# 3_buck.net
KiCad netlist of a schematic drawn in Altium Designer
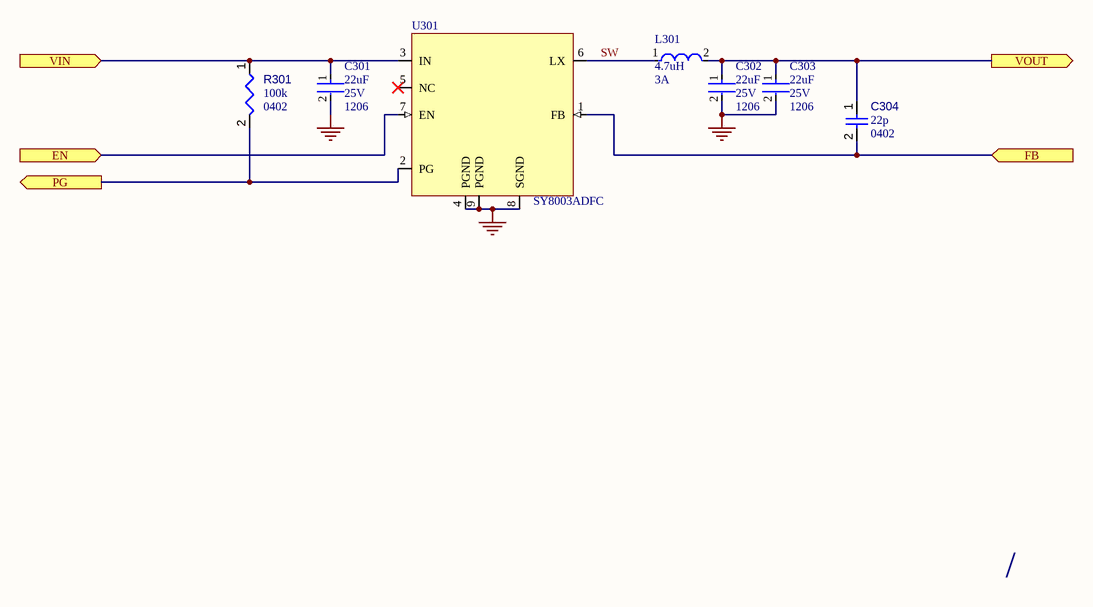
[diagram p0: 3 buck.SchDoc]

(export (version "E")
  (design (tool "Eeschema 10.0.6"))
  (components
    (comp (ref "C301")
      (value "TMK316BBJ226ML-T")
      (footprint "FP-1206-L_3_2_0_3-W_1_6_0-MFG")
      (description "None")
      (fields
        (field (name "CAPACITANCE") "22uF")
        (field (name "VOLTAGE RATING (DC)") "25V")
        (field (name "CASE CODE (IMPERIAL)") "1206")
        (field (name "TOLERANCE") "20%")
      )
      (libsource (lib "Altium Content Vault") (part "11868f565c42a9108669ba33697ecf6"))
    )
    (comp (ref "C302")
      (value "TMK316BBJ226ML-T")
      (footprint "FP-1206-L_3_2_0_3-W_1_6_0-MFG")
      (description "None")
      (fields
        (field (name "CAPACITANCE") "22uF")
        (field (name "VOLTAGE RATING (DC)") "25V")
        (field (name "CASE CODE (IMPERIAL)") "1206")
        (field (name "TOLERANCE") "20%")
      )
      (libsource (lib "Altium Content Vault") (part "11868f565c42a9108669ba33697ecf6"))
    )
    (comp (ref "C303")
      (value "TMK316BBJ226ML-T")
      (footprint "FP-1206-L_3_2_0_3-W_1_6_0-MFG")
      (description "None")
      (fields
        (field (name "CAPACITANCE") "22uF")
        (field (name "VOLTAGE RATING (DC)") "25V")
        (field (name "CASE CODE (IMPERIAL)") "1206")
        (field (name "TOLERANCE") "20%")
      )
      (libsource (lib "Altium Content Vault") (part "11868f565c42a9108669ba33697ecf6"))
    )
    (comp (ref "C304")
      (value "22p")
      (footprint "CAPC0402(1005)60_L")
      (description "Capacitor")
      (fields (field (name "CASE/PACKAGE") "0402") (field (name "Comment") "Capacitors,0402,22p"))
      (libsource (lib "UBC Uncrewed Aircraft Systems") (part "CAP-NP-2"))
    )
    (comp (ref "L301")
      (value "IHLP2525AHER4R7M01")
      (footprint "FP-IHLP-2525AH-FP_2_413x3-MFG")
      (description "Commercial Inductors, High Saturation Series 4.7uH 3A 78mΩ 20%")
      (fields
        (field (name "INDUCTANCE") "4.7uH")
        (field (name "TOLERANCE") "20%")
        (field (name "CURRENT RATING") "3A")
      )
      (libsource (lib "Altium Content Vault") (part "725321dda6339637d4d059423bc1c3c"))
    )
    (comp (ref "R301")
      (value "100k")
      (footprint "RESC0402(1005)_L")
      (description "Resistor")
      (fields
        (field (name "CASE/PACKAGE") "0402")
        (field (name "TOLERANCE") "1%")
        (field (name "Comment") "Resistors,0402,1%,100k")
      )
      (libsource (lib "UBC Uncrewed Aircraft Systems") (part "RES-2"))
    )
    (comp (ref "U301")
      (value "SY8003ADFC")
      (footprint "DFN2x2-8")
      (description "High Efficiency 5.5V, 3A Continuous, 1MHz Synchronous Step Down Regulator")
      (fields
        (field (name "MANUFACTURER") "Silergy")
        (field (name "MANUFACTURER PART NUMBER") "High Efficiency 5.5V, 3A continuous, 1MHz")
      )
      (libsource (lib "Phils") (part "SY8003ADFC"))
    )
  )
  (nets
    (net (code "1") (name "/EN") (class "Default")
      (node (ref "U301") (pin "7") (pinfunction "EN_7") (pintype "input"))
    )
    (net (code "2") (name "/FB") (class "Default")
      (node (ref "C304") (pin "2") (pinfunction "2_2") (pintype "passive"))
      (node (ref "U301") (pin "1") (pinfunction "FB_1") (pintype "input"))
    )
    (net (code "3") (name "/PG") (class "Default")
      (node (ref "R301") (pin "2") (pinfunction "2_2") (pintype "passive"))
      (node (ref "U301") (pin "2") (pinfunction "PG_2") (pintype "open_collector"))
    )
    (net (code "4") (name "/SW") (class "Default")
      (node (ref "L301") (pin "1") (pinfunction "1_1") (pintype "passive"))
      (node (ref "U301") (pin "6") (pinfunction "LX_6") (pintype "power_in"))
    )
    (net (code "5") (name "/VIN") (class "Default")
      (node (ref "C301") (pin "1") (pinfunction "1_1") (pintype "passive"))
      (node (ref "R301") (pin "1") (pinfunction "1_1") (pintype "passive"))
      (node (ref "U301") (pin "3") (pinfunction "IN_3") (pintype "power_in"))
    )
    (net (code "6") (name "/VOUT") (class "Default")
      (node (ref "C302") (pin "1") (pinfunction "1_1") (pintype "passive"))
      (node (ref "C303") (pin "1") (pinfunction "1_1") (pintype "passive"))
      (node (ref "C304") (pin "1") (pinfunction "1_1") (pintype "passive"))
      (node (ref "L301") (pin "2") (pinfunction "2_2") (pintype "passive"))
    )
    (net (code "7") (name "GND") (class "Default")
      (node (ref "C301") (pin "2") (pinfunction "2_2") (pintype "passive"))
      (node (ref "C302") (pin "2") (pinfunction "2_2") (pintype "passive"))
      (node (ref "C303") (pin "2") (pinfunction "2_2") (pintype "passive"))
      (node (ref "U301") (pin "4") (pinfunction "PGND_4") (pintype "power_in"))
      (node (ref "U301") (pin "8") (pinfunction "SGND_8") (pintype "power_in"))
      (node (ref "U301") (pin "9") (pinfunction "PGND_9") (pintype "power_in"))
    )
    (net (code "8") (name "unconnected-(U301-NC-Pad5)") (class "Default")
      (node (ref "U301") (pin "5") (pinfunction "NC_5") (pintype "passive+no_connect"))
    )
  )
)
